# CFD.net
KiCad netlist of a schematic drawn in Altium Designer
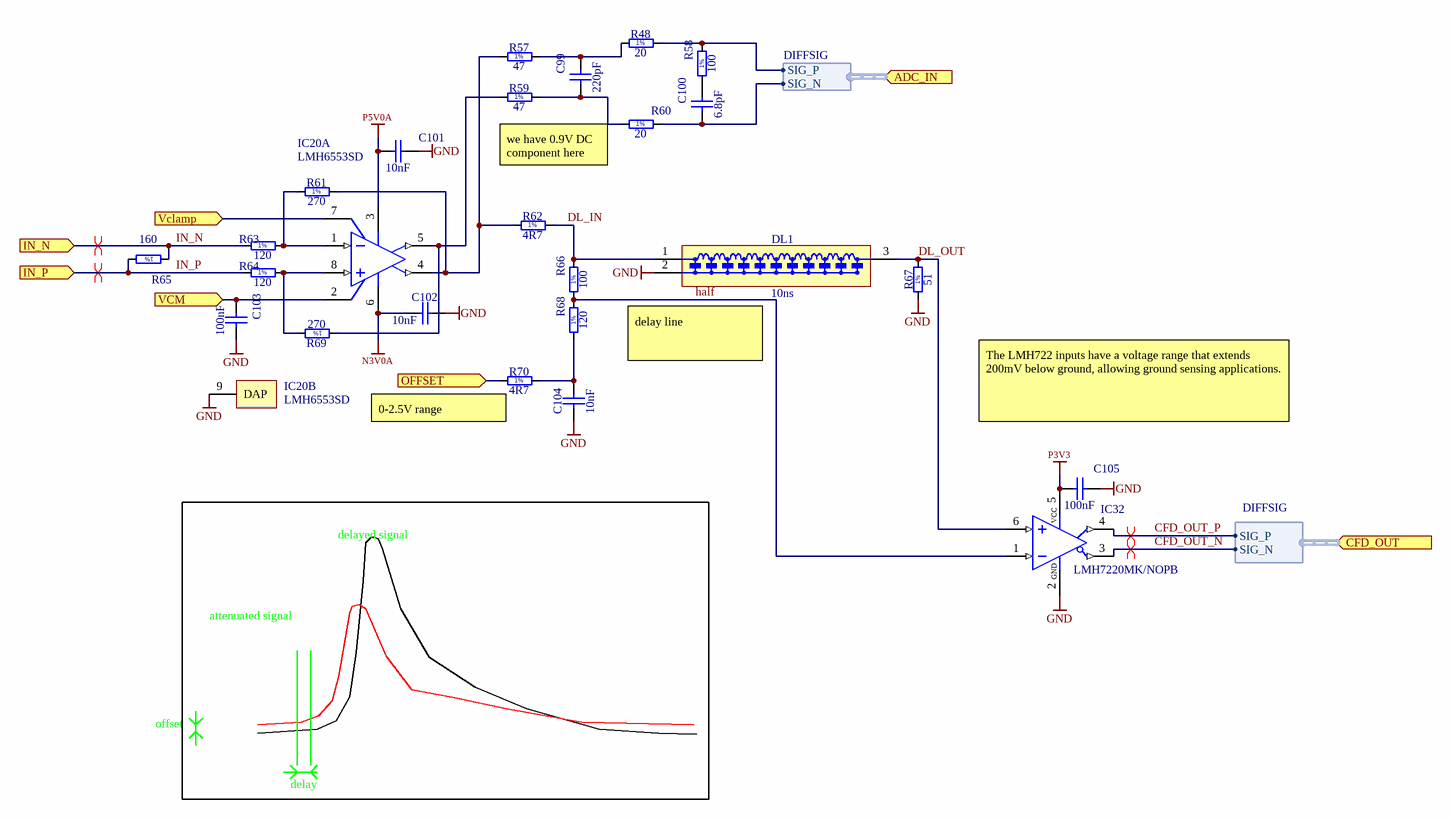
[diagram p0: CFD.SchDoc]

(export (version "E")
  (design (tool "Eeschema 10.0.6"))
  (components
    (comp (ref "C99")
      (value "220pF")
      (footprint "CAPC1005X55N")
      (description "Non-polarised capacitor")
      (fields
        (field (name "PART NUMBER") "CC0402_220PF_50V_5%_C0G")
        (field (name "MANUFACTURER") "GENERIC")
        (field (name "AUTHOR") "CERN DEM JLC")
      )
      (libsource (lib "Capacitors") (part "Capacitor - non polarized"))
    )
    (comp (ref "C100")
      (value "6.8pF")
      (footprint "CAPC1005X70N")
      (description "Non-polarised capacitor")
      (fields
        (field (name "PART NUMBER") "CC0402_6.8PF_50V_0.25PF_C0G_VISHAY_VJ_NON-MAGNETIC")
        (field (name "VOLTAGE") "50V")
        (field (name "AUTHOR") "CERN DEM MR")
      )
      (libsource (lib "Capacitors") (part "Capacitor - non polarized"))
    )
    (comp (ref "C101")
      (value "10nF")
      (footprint "CAPC0603X33N")
      (description "Non-polarised capacitor")
      (fields
        (field (name "PART NUMBER") "CC0201_10NF_10V_10%_X5R")
        (field (name "VOLTAGE") "10V")
        (field (name "AUTHOR") "CERN DEM JLC")
      )
      (libsource (lib "Capacitors") (part "Capacitor - non polarized"))
    )
    (comp (ref "C102")
      (value "10nF")
      (footprint "CAPC0603X33N")
      (description "Non-polarised capacitor")
      (fields
        (field (name "PART NUMBER") "CC0201_10NF_10V_10%_X5R")
        (field (name "VOLTAGE") "10V")
        (field (name "AUTHOR") "CERN DEM JLC")
      )
      (libsource (lib "Capacitors") (part "Capacitor - non polarized"))
    )
    (comp (ref "C103")
      (value "100nF")
      (footprint "CAPC0603X33N")
      (description "Non-polarised capacitor")
      (fields
        (field (name "PART NUMBER") "CC0201_100NF_6.3V_10%_X5R")
        (field (name "VOLTAGE") "6.3V")
        (field (name "AUTHOR") "CERN DEM JLC")
      )
      (libsource (lib "Capacitors") (part "Capacitor - non polarized"))
    )
    (comp (ref "C104")
      (value "10nF")
      (footprint "CAPC1005X55N")
      (description "Non-polarised capacitor")
      (fields
        (field (name "PART NUMBER") "CC0402_10NF_16V_10%_X7R")
        (field (name "VOLTAGE") "16V")
        (field (name "AUTHOR") "CERN DEM JLC")
      )
      (libsource (lib "Capacitors") (part "Capacitor - non polarized"))
    )
    (comp (ref "C105")
      (value "100nF")
      (footprint "CAPC0603X33N")
      (description "Non-polarised capacitor")
      (fields
        (field (name "PART NUMBER") "CC0201_100NF_6.3V_10%_X5R")
        (field (name "VOLTAGE") "6.3V")
        (field (name "AUTHOR") "CERN DEM JLC")
      )
      (libsource (lib "Capacitors") (part "Capacitor - non polarized"))
    )
    (comp (ref "DL1")
      (value "10ns")
      (footprint "DS1L")
      (description "Fixed SIP Delay Line")
      (fields (field (name "PART NUMBER") "DS1L") (field (name "AUTHOR") "GK"))
      (libsource (lib "LIBRARY_SCH") (part "DL_DS1L"))
    )
    (comp (ref "IC20")
      (value "LMH6553SD")
      (footprint "SDA08C")
      (description "900 MHz Fully Differential Amplifier with Output Limiting Clamp, 8-pin LLP")
      (fields (field (name "MANUFACTURER") "National Semiconductor"))
      (libsource (lib "Altium Content Vault") (part "AMP-DIFA-LMH6553-9"))
    )
    (comp (ref "IC32")
      (value "LMH7220MK/NOPB")
      (footprint "SOT95P285X100-6N")
      (description "High Speed Comparator with LVDS Output")
      (fields (field (name "MANUFACTURER") "NATIONAL SEMICONDUCTOR") (field (name "AUTHOR") "CERN DEM JLC"))
      (libsource (lib "ICs And Semiconductors") (part "LMH7220"))
    )
    (comp (ref "R48")
      (value "20")
      (footprint "RESC1005X40N")
      (description "Resistor - 1%")
      (fields
        (field (name "PART NUMBER") "R0402_20R_1%_0.0625W_100PPM")
        (field (name "POWER") "0.0625W")
        (field (name "AUTHOR") "CERN DEM JLC")
      )
      (libsource (lib "Resistors") (part "Resistor - 1%"))
    )
    (comp (ref "R57")
      (value "47")
      (footprint "RESC1005X40N")
      (description "Resistor - 1%")
      (fields
        (field (name "PART NUMBER") "R0402_47R_1%_0.0625W_100PPM")
        (field (name "POWER") "0.0625W")
        (field (name "AUTHOR") "CERN DEM JLC")
      )
      (libsource (lib "Resistors") (part "Resistor - 1%"))
    )
    (comp (ref "R58")
      (value "100")
      (footprint "RESC0603X28N")
      (description "Resistor - 1%")
      (fields
        (field (name "PART NUMBER") "R0201_100R_1%_0.05W_200PPM")
        (field (name "POWER") "0.05W")
        (field (name "AUTHOR") "CERN DEM JLC")
      )
      (libsource (lib "Resistors") (part "Resistor - 1%"))
    )
    (comp (ref "R59")
      (value "47")
      (footprint "RESC1005X40N")
      (description "Resistor - 1%")
      (fields
        (field (name "PART NUMBER") "R0402_47R_1%_0.0625W_100PPM")
        (field (name "POWER") "0.0625W")
        (field (name "AUTHOR") "CERN DEM JLC")
      )
      (libsource (lib "Resistors") (part "Resistor - 1%"))
    )
    (comp (ref "R60")
      (value "20")
      (footprint "RESC1005X40N")
      (description "Resistor - 1%")
      (fields
        (field (name "PART NUMBER") "R0402_20R_1%_0.0625W_100PPM")
        (field (name "POWER") "0.0625W")
        (field (name "AUTHOR") "CERN DEM JLC")
      )
      (libsource (lib "Resistors") (part "Resistor - 1%"))
    )
    (comp (ref "R61")
      (value "270")
      (footprint "RESC1005X40N")
      (description "Resistor - 1%")
      (fields
        (field (name "PART NUMBER") "R0402_270R_1%_0.0625W_100PPM")
        (field (name "POWER") "0.0625W")
        (field (name "AUTHOR") "CERN DEM JLC")
      )
      (libsource (lib "Resistors") (part "Resistor - 1%"))
    )
    (comp (ref "R62")
      (value "4R7")
      (footprint "RESC1005X40N")
      (description "Resistor - 1%")
      (fields
        (field (name "PART NUMBER") "R0402_4R7_1%_0.0625W_200PPM")
        (field (name "POWER") "0.0625W")
        (field (name "AUTHOR") "CERN DEM JLC")
      )
      (libsource (lib "Resistors") (part "Resistor - 1%"))
    )
    (comp (ref "R63")
      (value "120")
      (footprint "RESC1005X40N")
      (description "Resistor - 1%")
      (fields
        (field (name "PART NUMBER") "R0402_120R_1%_0.0625W_100PPM")
        (field (name "POWER") "0.0625W")
        (field (name "AUTHOR") "CERN DEM JLC")
      )
      (libsource (lib "Resistors") (part "Resistor - 1%"))
    )
    (comp (ref "R64")
      (value "120")
      (footprint "RESC1005X40N")
      (description "Resistor - 1%")
      (fields
        (field (name "PART NUMBER") "R0402_120R_1%_0.0625W_100PPM")
        (field (name "POWER") "0.0625W")
        (field (name "AUTHOR") "CERN DEM JLC")
      )
      (libsource (lib "Resistors") (part "Resistor - 1%"))
    )
    (comp (ref "R65")
      (value "160")
      (footprint "RESC1005X40N")
      (description "Resistor - 1%")
      (fields
        (field (name "PART NUMBER") "R0402_160R_1%_0.0625W_100PPM")
        (field (name "POWER") "0.0625W")
        (field (name "AUTHOR") "CERN DEM JLC")
      )
      (libsource (lib "Resistors") (part "Resistor - 1%"))
    )
    (comp (ref "R66")
      (value "100")
      (footprint "RESC0603X28N")
      (description "Resistor - 1%")
      (fields
        (field (name "PART NUMBER") "R0201_100R_1%_0.05W_200PPM")
        (field (name "POWER") "0.05W")
        (field (name "AUTHOR") "CERN DEM JLC")
      )
      (libsource (lib "Resistors") (part "Resistor - 1%"))
    )
    (comp (ref "R67")
      (value "51")
      (footprint "RESC1005X40N")
      (description "Resistor - 1%")
      (fields
        (field (name "PART NUMBER") "R0402_51R_1%_0.0625W_100PPM")
        (field (name "POWER") "0.0625W")
        (field (name "AUTHOR") "CERN DEM JLC")
      )
      (libsource (lib "Resistors") (part "Resistor - 1%"))
    )
    (comp (ref "R68")
      (value "120")
      (footprint "RESC1005X40N")
      (description "Resistor - 1%")
      (fields
        (field (name "PART NUMBER") "R0402_120R_1%_0.0625W_100PPM")
        (field (name "POWER") "0.0625W")
        (field (name "AUTHOR") "CERN DEM JLC")
      )
      (libsource (lib "Resistors") (part "Resistor - 1%"))
    )
    (comp (ref "R69")
      (value "270")
      (footprint "RESC1005X40N")
      (description "Resistor - 1%")
      (fields
        (field (name "PART NUMBER") "R0402_270R_1%_0.0625W_100PPM")
        (field (name "POWER") "0.0625W")
        (field (name "AUTHOR") "CERN DEM JLC")
      )
      (libsource (lib "Resistors") (part "Resistor - 1%"))
    )
    (comp (ref "R70")
      (value "4R7")
      (footprint "RESC1005X40N")
      (description "Resistor - 1%")
      (fields
        (field (name "PART NUMBER") "R0402_4R7_1%_0.0625W_200PPM")
        (field (name "POWER") "0.0625W")
        (field (name "AUTHOR") "CERN DEM JLC")
      )
      (libsource (lib "Resistors") (part "Resistor - 1%"))
    )
  )
  (nets
    (net (code "2") (name "/CFD_OUT_N") (class "Default")
      (node (ref "IC32") (pin "3") (pinfunction "VOUT~{Q}_3") (pintype "output"))
    )
    (net (code "3") (name "/CFD_OUT_P") (class "Default")
      (node (ref "IC32") (pin "4") (pinfunction "VOUTQ_4") (pintype "output"))
    )
    (net (code "4") (name "/DL_IN") (class "Default")
      (node (ref "DL1") (pin "1") (pinfunction "GND_1") (pintype "power_in"))
      (node (ref "R62") (pin "2") (pinfunction "2_2") (pintype "passive"))
      (node (ref "R66") (pin "2") (pinfunction "2_2") (pintype "passive"))
    )
    (net (code "5") (name "/DL_OUT") (class "Default")
      (node (ref "DL1") (pin "3") (pinfunction "OUT_3") (pintype "passive"))
      (node (ref "IC32") (pin "6") (pinfunction "IN+_6") (pintype "input"))
      (node (ref "R67") (pin "2") (pinfunction "2_2") (pintype "passive"))
    )
    (net (code "6") (name "/IN_N") (class "Default")
      (node (ref "R63") (pin "1") (pinfunction "1_1") (pintype "passive"))
      (node (ref "R65") (pin "1") (pinfunction "1_1") (pintype "passive"))
    )
    (net (code "7") (name "/IN_P") (class "Default")
      (node (ref "R64") (pin "1") (pinfunction "1_1") (pintype "passive"))
      (node (ref "R65") (pin "2") (pinfunction "2_2") (pintype "passive"))
    )
    (net (code "8") (name "/OFFSET") (class "Default")
      (node (ref "R70") (pin "1") (pinfunction "1_1") (pintype "passive"))
    )
    (net (code "9") (name "/VCM") (class "Default")
      (node (ref "C103") (pin "1") (pinfunction "1_1") (pintype "passive"))
      (node (ref "IC20") (pin "2") (pinfunction "VCM_2") (pintype "passive"))
    )
    (net (code "10") (name "/Vclamp") (class "Default")
      (node (ref "IC20") (pin "7") (pinfunction "VCLAMP_7") (pintype "passive"))
    )
    (net (code "11") (name "/half") (class "Default")
      (node (ref "IC32") (pin "1") (pinfunction "IN-_1") (pintype "input"))
      (node (ref "R66") (pin "1") (pinfunction "1_1") (pintype "passive"))
      (node (ref "R68") (pin "2") (pinfunction "2_2") (pintype "passive"))
    )
    (net (code "13") (name "GND") (class "Default")
      (node (ref "C101") (pin "2") (pinfunction "2_2") (pintype "passive"))
      (node (ref "C102") (pin "2") (pinfunction "2_2") (pintype "passive"))
      (node (ref "C103") (pin "2") (pinfunction "2_2") (pintype "passive"))
      (node (ref "C104") (pin "1") (pinfunction "1_1") (pintype "passive"))
      (node (ref "C105") (pin "2") (pinfunction "2_2") (pintype "passive"))
      (node (ref "DL1") (pin "2") (pinfunction "IN_2") (pintype "passive"))
      (node (ref "IC20") (pin "9") (pinfunction "DAP_9") (pintype "passive"))
      (node (ref "IC32") (pin "2") (pinfunction "GND_2") (pintype "power_in"))
      (node (ref "R67") (pin "1") (pinfunction "1_1") (pintype "passive"))
    )
    (net (code "14") (name "N3V0A") (class "Default")
      (node (ref "C102") (pin "1") (pinfunction "1_1") (pintype "passive"))
      (node (ref "IC20") (pin "6") (pinfunction "V-_6") (pintype "power_in"))
    )
    (net (code "15") (name "Net-(C99-Pad1)") (class "Default")
      (node (ref "C99") (pin "1") (pinfunction "1_1") (pintype "passive"))
      (node (ref "R59") (pin "2") (pinfunction "2_2") (pintype "passive"))
      (node (ref "R60") (pin "1") (pinfunction "1_1") (pintype "passive"))
    )
    (net (code "16") (name "Net-(C99-Pad2)") (class "Default")
      (node (ref "C99") (pin "2") (pinfunction "2_2") (pintype "passive"))
      (node (ref "R48") (pin "1") (pinfunction "1_1") (pintype "passive"))
      (node (ref "R57") (pin "2") (pinfunction "2_2") (pintype "passive"))
    )
    (net (code "17") (name "Net-(C100-Pad1)") (class "Default")
      (node (ref "C100") (pin "1") (pinfunction "1_1") (pintype "passive"))
      (node (ref "R60") (pin "2") (pinfunction "2_2") (pintype "passive"))
    )
    (net (code "18") (name "Net-(C100-Pad2)") (class "Default")
      (node (ref "C100") (pin "2") (pinfunction "2_2") (pintype "passive"))
      (node (ref "R58") (pin "1") (pinfunction "1_1") (pintype "passive"))
    )
    (net (code "19") (name "Net-(C104-Pad2)") (class "Default")
      (node (ref "C104") (pin "2") (pinfunction "2_2") (pintype "passive"))
      (node (ref "R68") (pin "1") (pinfunction "1_1") (pintype "passive"))
      (node (ref "R70") (pin "2") (pinfunction "2_2") (pintype "passive"))
    )
    (net (code "20") (name "Net-(IC20A-IN+)") (class "Default")
      (node (ref "IC20") (pin "8") (pinfunction "IN+_8") (pintype "input"))
      (node (ref "R64") (pin "2") (pinfunction "2_2") (pintype "passive"))
      (node (ref "R69") (pin "2") (pinfunction "2_2") (pintype "passive"))
    )
    (net (code "21") (name "Net-(IC20A-IN-)") (class "Default")
      (node (ref "IC20") (pin "1") (pinfunction "IN-_1") (pintype "input"))
      (node (ref "R61") (pin "1") (pinfunction "1_1") (pintype "passive"))
      (node (ref "R63") (pin "2") (pinfunction "2_2") (pintype "passive"))
    )
    (net (code "22") (name "Net-(IC20A-OUT+)") (class "Default")
      (node (ref "IC20") (pin "4") (pinfunction "OUT+_4") (pintype "output"))
      (node (ref "R57") (pin "1") (pinfunction "1_1") (pintype "passive"))
      (node (ref "R61") (pin "2") (pinfunction "2_2") (pintype "passive"))
      (node (ref "R62") (pin "1") (pinfunction "1_1") (pintype "passive"))
    )
    (net (code "23") (name "Net-(IC20A-OUT-)") (class "Default")
      (node (ref "IC20") (pin "5") (pinfunction "OUT-_5") (pintype "output"))
      (node (ref "R59") (pin "1") (pinfunction "1_1") (pintype "passive"))
      (node (ref "R69") (pin "1") (pinfunction "1_1") (pintype "passive"))
    )
    (net (code "24") (name "Net-(R48-Pad2)") (class "Default")
      (node (ref "R48") (pin "2") (pinfunction "2_2") (pintype "passive"))
      (node (ref "R58") (pin "2") (pinfunction "2_2") (pintype "passive"))
    )
    (net (code "25") (name "P3V3") (class "Default")
      (node (ref "C105") (pin "1") (pinfunction "1_1") (pintype "passive"))
      (node (ref "IC32") (pin "5") (pinfunction "VCC_5") (pintype "power_in"))
    )
    (net (code "26") (name "P5V0A") (class "Default")
      (node (ref "C101") (pin "1") (pinfunction "1_1") (pintype "passive"))
      (node (ref "IC20") (pin "3") (pinfunction "V+_3") (pintype "power_in"))
    )
  )
)
